# tracksoar_programmer.net
KiCad netlist of a schematic drawn in EAGLE
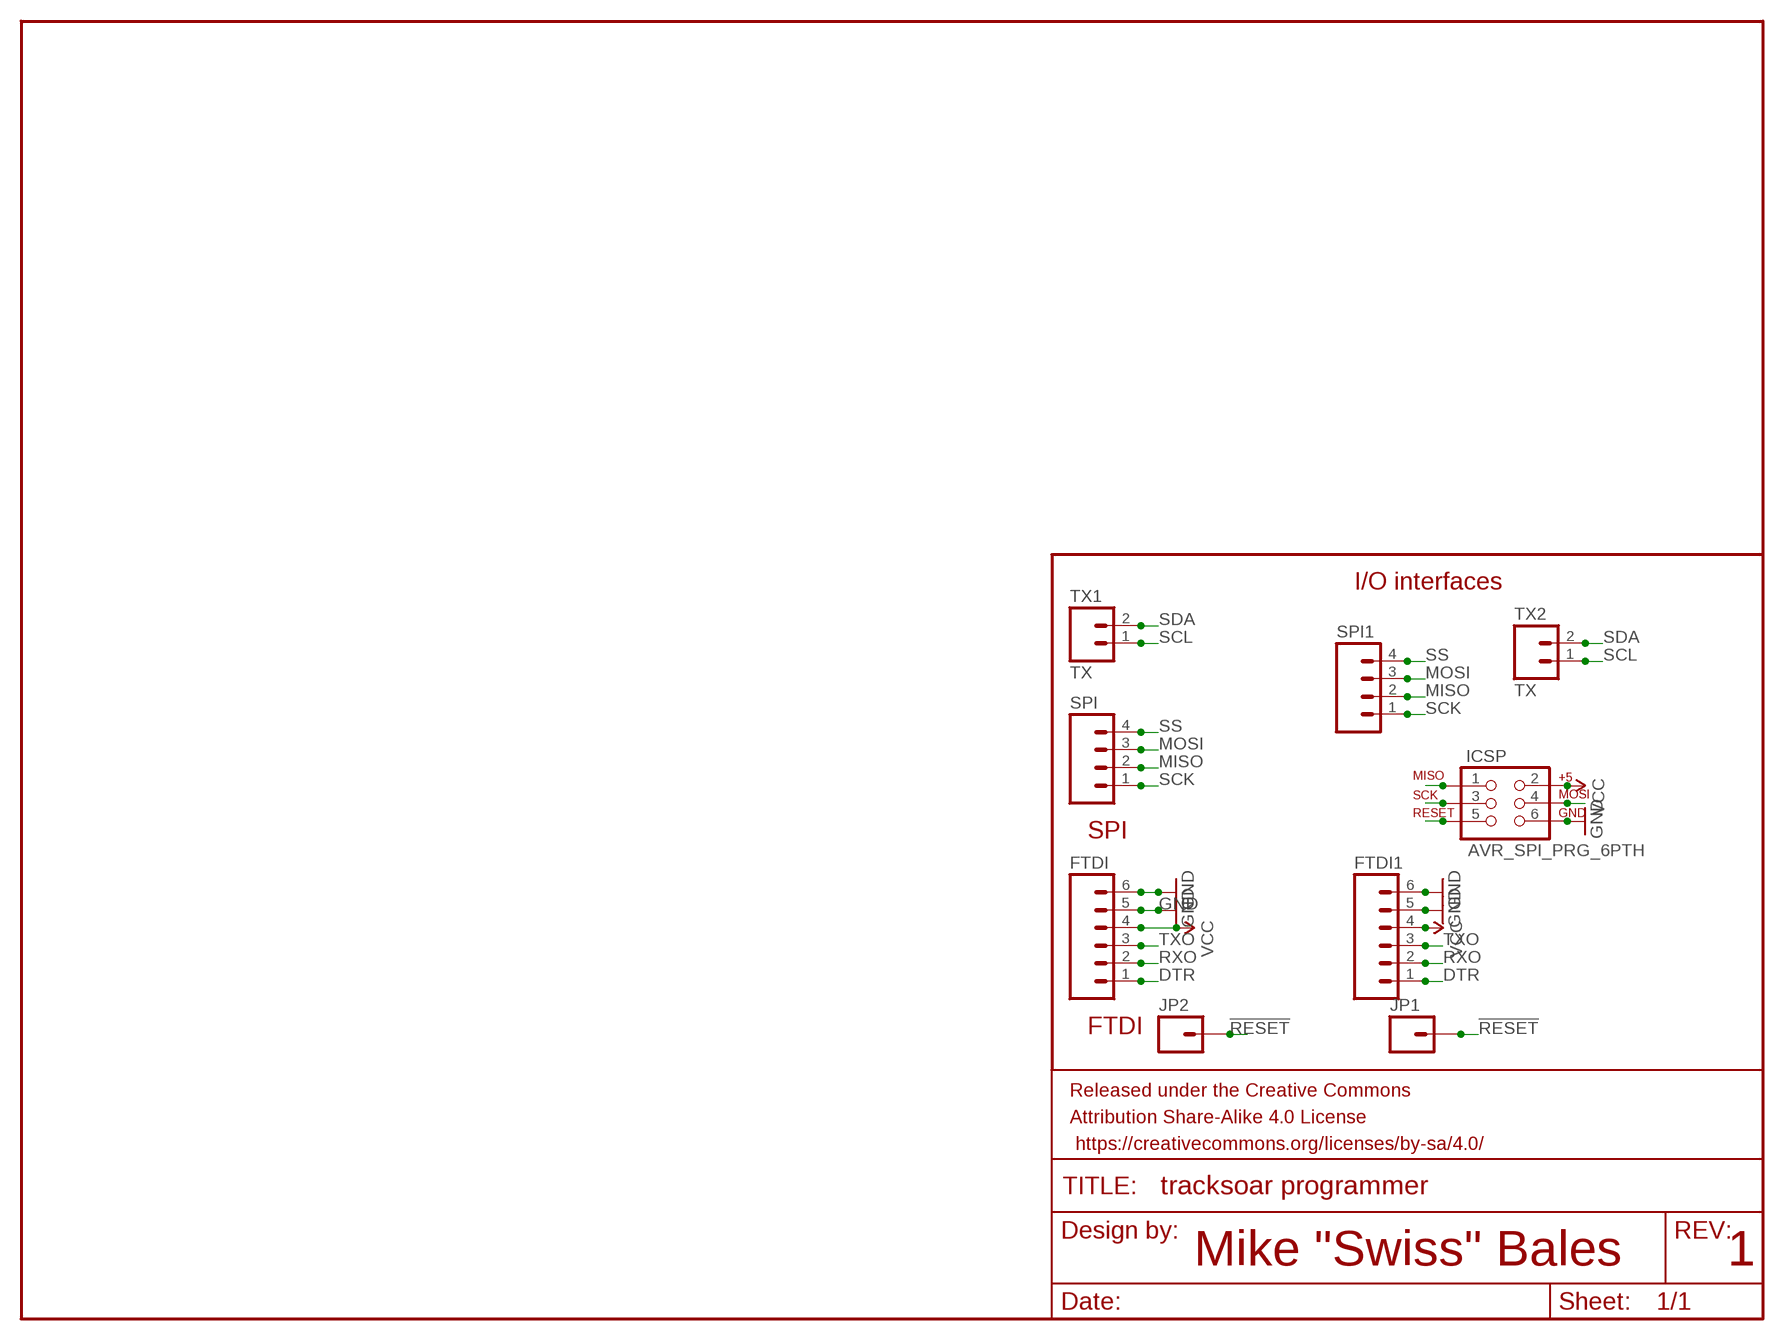
[diagram p0: schematic, sheet 1]

(export (version "E")
  (design (tool "Eeschema 10.0.6"))
  (components
    (comp (ref "FRAME1")
      (value "FRAME-LETTER")
      (footprint "eagle-import:CREATIVE_COMMONS")
      (libsource (lib "eagle-import") (part "FRAME-LETTER"))
    )
    (comp (ref "FTDI")
      (value "M06NO_SILK_FEMALE_PTH")
      (footprint "eagle-import:1X06_NO_SILK")
      (libsource (lib "eagle-import") (part "M06NO_SILK_FEMALE_PTH"))
    )
    (comp (ref "FTDI1")
      (value "M06NO_SILK_FEMALE_PTH")
      (footprint "eagle-import:1X06_NO_SILK")
      (libsource (lib "eagle-import") (part "M06NO_SILK_FEMALE_PTH"))
    )
    (comp (ref "ICSP")
      (value "AVR_SPI_PRG_6PTH")
      (footprint "eagle-import:2X3")
      (libsource (lib "eagle-import") (part "AVR_SPI_PRG_6PTH"))
    )
    (comp (ref "JP1")
      (value "M01PTH")
      (footprint "eagle-import:1X01")
      (libsource (lib "eagle-import") (part "M01PTH"))
    )
    (comp (ref "JP2")
      (value "M01PTH")
      (footprint "eagle-import:1X01")
      (libsource (lib "eagle-import") (part "M01PTH"))
    )
    (comp (ref "SPI")
      (value "M04JST-PTH-VERT")
      (footprint "eagle-import:JST-4-PTH-VERT")
      (libsource (lib "eagle-import") (part "M04JST-PTH-VERT"))
    )
    (comp (ref "SPI1")
      (value "M04JST-PTH-VERT")
      (footprint "eagle-import:JST-4-PTH-VERT")
      (libsource (lib "eagle-import") (part "M04JST-PTH-VERT"))
    )
    (comp (ref "TX1")
      (value "TX")
      (footprint "eagle-import:JST-2-PTH-VERT")
      (libsource (lib "eagle-import") (part "M02JST-PTH-VERT"))
    )
    (comp (ref "TX2")
      (value "TX")
      (footprint "eagle-import:JST-2-PTH-VERT")
      (libsource (lib "eagle-import") (part "M02JST-PTH-VERT"))
    )
  )
  (nets
    (net (code "1") (name "/DTR") (class "Default")
      (node (ref "FTDI") (pin "1") (pinfunction "1_1") (pintype "passive"))
      (node (ref "FTDI1") (pin "1") (pinfunction "1_1") (pintype "passive"))
    )
    (net (code "2") (name "/MISO") (class "Default")
      (node (ref "ICSP") (pin "1") (pinfunction "1_1") (pintype "passive"))
      (node (ref "SPI") (pin "2") (pinfunction "2_2") (pintype "passive"))
      (node (ref "SPI1") (pin "2") (pinfunction "2_2") (pintype "passive"))
    )
    (net (code "3") (name "/MOSI") (class "Default")
      (node (ref "ICSP") (pin "4") (pinfunction "4_4") (pintype "passive"))
      (node (ref "SPI") (pin "3") (pinfunction "3_3") (pintype "passive"))
      (node (ref "SPI1") (pin "3") (pinfunction "3_3") (pintype "passive"))
    )
    (net (code "4") (name "/RXO") (class "Default")
      (node (ref "FTDI") (pin "2") (pinfunction "2_2") (pintype "passive"))
      (node (ref "FTDI1") (pin "2") (pinfunction "2_2") (pintype "passive"))
    )
    (net (code "5") (name "/SCK") (class "Default")
      (node (ref "ICSP") (pin "3") (pinfunction "3_3") (pintype "passive"))
      (node (ref "SPI") (pin "1") (pinfunction "1_1") (pintype "passive"))
      (node (ref "SPI1") (pin "1") (pinfunction "1_1") (pintype "passive"))
    )
    (net (code "6") (name "/SCL") (class "Default")
      (node (ref "TX1") (pin "1") (pinfunction "1_1") (pintype "passive"))
      (node (ref "TX2") (pin "1") (pinfunction "1_1") (pintype "passive"))
    )
    (net (code "7") (name "/SDA") (class "Default")
      (node (ref "TX1") (pin "2") (pinfunction "2_2") (pintype "passive"))
      (node (ref "TX2") (pin "2") (pinfunction "2_2") (pintype "passive"))
    )
    (net (code "8") (name "/SS") (class "Default")
      (node (ref "SPI") (pin "4") (pinfunction "4_4") (pintype "passive"))
      (node (ref "SPI1") (pin "4") (pinfunction "4_4") (pintype "passive"))
    )
    (net (code "9") (name "/TXO") (class "Default")
      (node (ref "FTDI") (pin "3") (pinfunction "3_3") (pintype "passive"))
      (node (ref "FTDI1") (pin "3") (pinfunction "3_3") (pintype "passive"))
    )
    (net (code "10") (name "/~{RESET}") (class "Default")
      (node (ref "ICSP") (pin "5") (pinfunction "5_5") (pintype "passive"))
      (node (ref "JP1") (pin "1") (pinfunction "1_1") (pintype "passive"))
      (node (ref "JP2") (pin "1") (pinfunction "1_1") (pintype "passive"))
    )
    (net (code "11") (name "GND") (class "Default")
      (node (ref "FTDI") (pin "5") (pinfunction "5_5") (pintype "passive"))
      (node (ref "FTDI") (pin "6") (pinfunction "6_6") (pintype "passive"))
      (node (ref "FTDI1") (pin "5") (pinfunction "5_5") (pintype "passive"))
      (node (ref "FTDI1") (pin "6") (pinfunction "6_6") (pintype "passive"))
      (node (ref "ICSP") (pin "6") (pinfunction "6_6") (pintype "passive"))
    )
    (net (code "12") (name "VCC") (class "Default")
      (node (ref "FTDI") (pin "4") (pinfunction "4_4") (pintype "passive"))
      (node (ref "FTDI1") (pin "4") (pinfunction "4_4") (pintype "passive"))
      (node (ref "ICSP") (pin "2") (pinfunction "2_2") (pintype "passive"))
    )
  )
)
